# band-stop_filter.net
KiCad netlist of a schematic drawn in Altium Designer
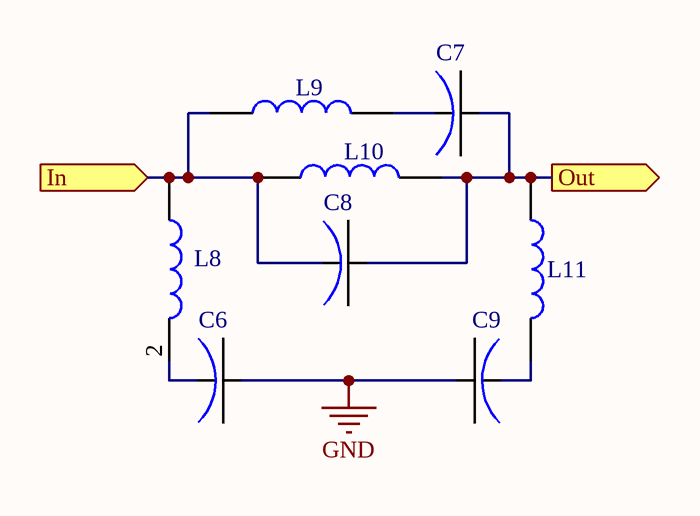
[diagram p0: band-stop_filter.SchDoc]

(export (version "E")
  (design (tool "Eeschema 10.0.6"))
  (components
    (comp (ref "C6") (value "Cap") (footprint "C0805") (libsource (lib "Integrated_Library1") (part "Cap")))
    (comp (ref "C7") (value "Cap") (footprint "C0603") (libsource (lib "Integrated_Library1") (part "Cap")))
    (comp (ref "C8") (value "Cap") (footprint "C1206") (libsource (lib "Integrated_Library1") (part "Cap")))
    (comp (ref "C9") (value "Cap") (footprint "C0805") (libsource (lib "Integrated_Library1") (part "Cap")))
    (comp (ref "L8")
      (value "L1008")
      (footprint "L1008")
      (description "Vishay IMC1008E2RJ7")
      (libsource (lib "") (part "L1008_1"))
    )
    (comp (ref "L9")
      (value "L1812")
      (footprint "L1812")
      (description "Vishay IMC1812ER150J")
      (libsource (lib "БИБЛИОТЕКА") (part "L1812"))
    )
    (comp (ref "L10")
      (value "L1008")
      (footprint "L1008")
      (description "Vishay IMC1008E2RJ7")
      (libsource (lib "Integrated_Library1") (part "L1008"))
    )
    (comp (ref "L11")
      (value "L1008")
      (footprint "L1008")
      (description "Vishay IMC1008E2RJ7")
      (libsource (lib "Integrated_Library1") (part "L1008"))
    )
  )
  (nets
    (net (code "1") (name "/In") (class "Default")
      (node (ref "C8") (pin "1") (pinfunction "1_1") (pintype "passive"))
      (node (ref "L10") (pin "1") (pinfunction "1_1") (pintype "passive"))
      (node (ref "L8") (pin "1") (pinfunction "1_1") (pintype "passive"))
      (node (ref "L9") (pin "1") (pinfunction "1_1") (pintype "passive"))
    )
    (net (code "2") (name "/Out") (class "Default")
      (node (ref "C7") (pin "2") (pinfunction "2_2") (pintype "passive"))
      (node (ref "C8") (pin "2") (pinfunction "2_2") (pintype "passive"))
      (node (ref "L10") (pin "2") (pinfunction "2_2") (pintype "passive"))
      (node (ref "L11") (pin "1") (pinfunction "1_1") (pintype "passive"))
    )
    (net (code "3") (name "GND") (class "Default")
      (node (ref "C6") (pin "2") (pinfunction "2_2") (pintype "passive"))
      (node (ref "C9") (pin "2") (pinfunction "2_2") (pintype "passive"))
    )
    (net (code "4") (name "Net-(C6-Pad1)") (class "Default")
      (node (ref "C6") (pin "1") (pinfunction "1_1") (pintype "passive"))
      (node (ref "L8") (pin "2") (pinfunction "2_2") (pintype "passive"))
    )
    (net (code "5") (name "Net-(C7-Pad1)") (class "Default")
      (node (ref "C7") (pin "1") (pinfunction "1_1") (pintype "passive"))
      (node (ref "L9") (pin "2") (pinfunction "2_2") (pintype "passive"))
    )
    (net (code "6") (name "Net-(C9-Pad1)") (class "Default")
      (node (ref "C9") (pin "1") (pinfunction "1_1") (pintype "passive"))
      (node (ref "L11") (pin "2") (pinfunction "2_2") (pintype "passive"))
    )
  )
)
